# ServoController.net
KiCad netlist of a schematic drawn in EAGLE
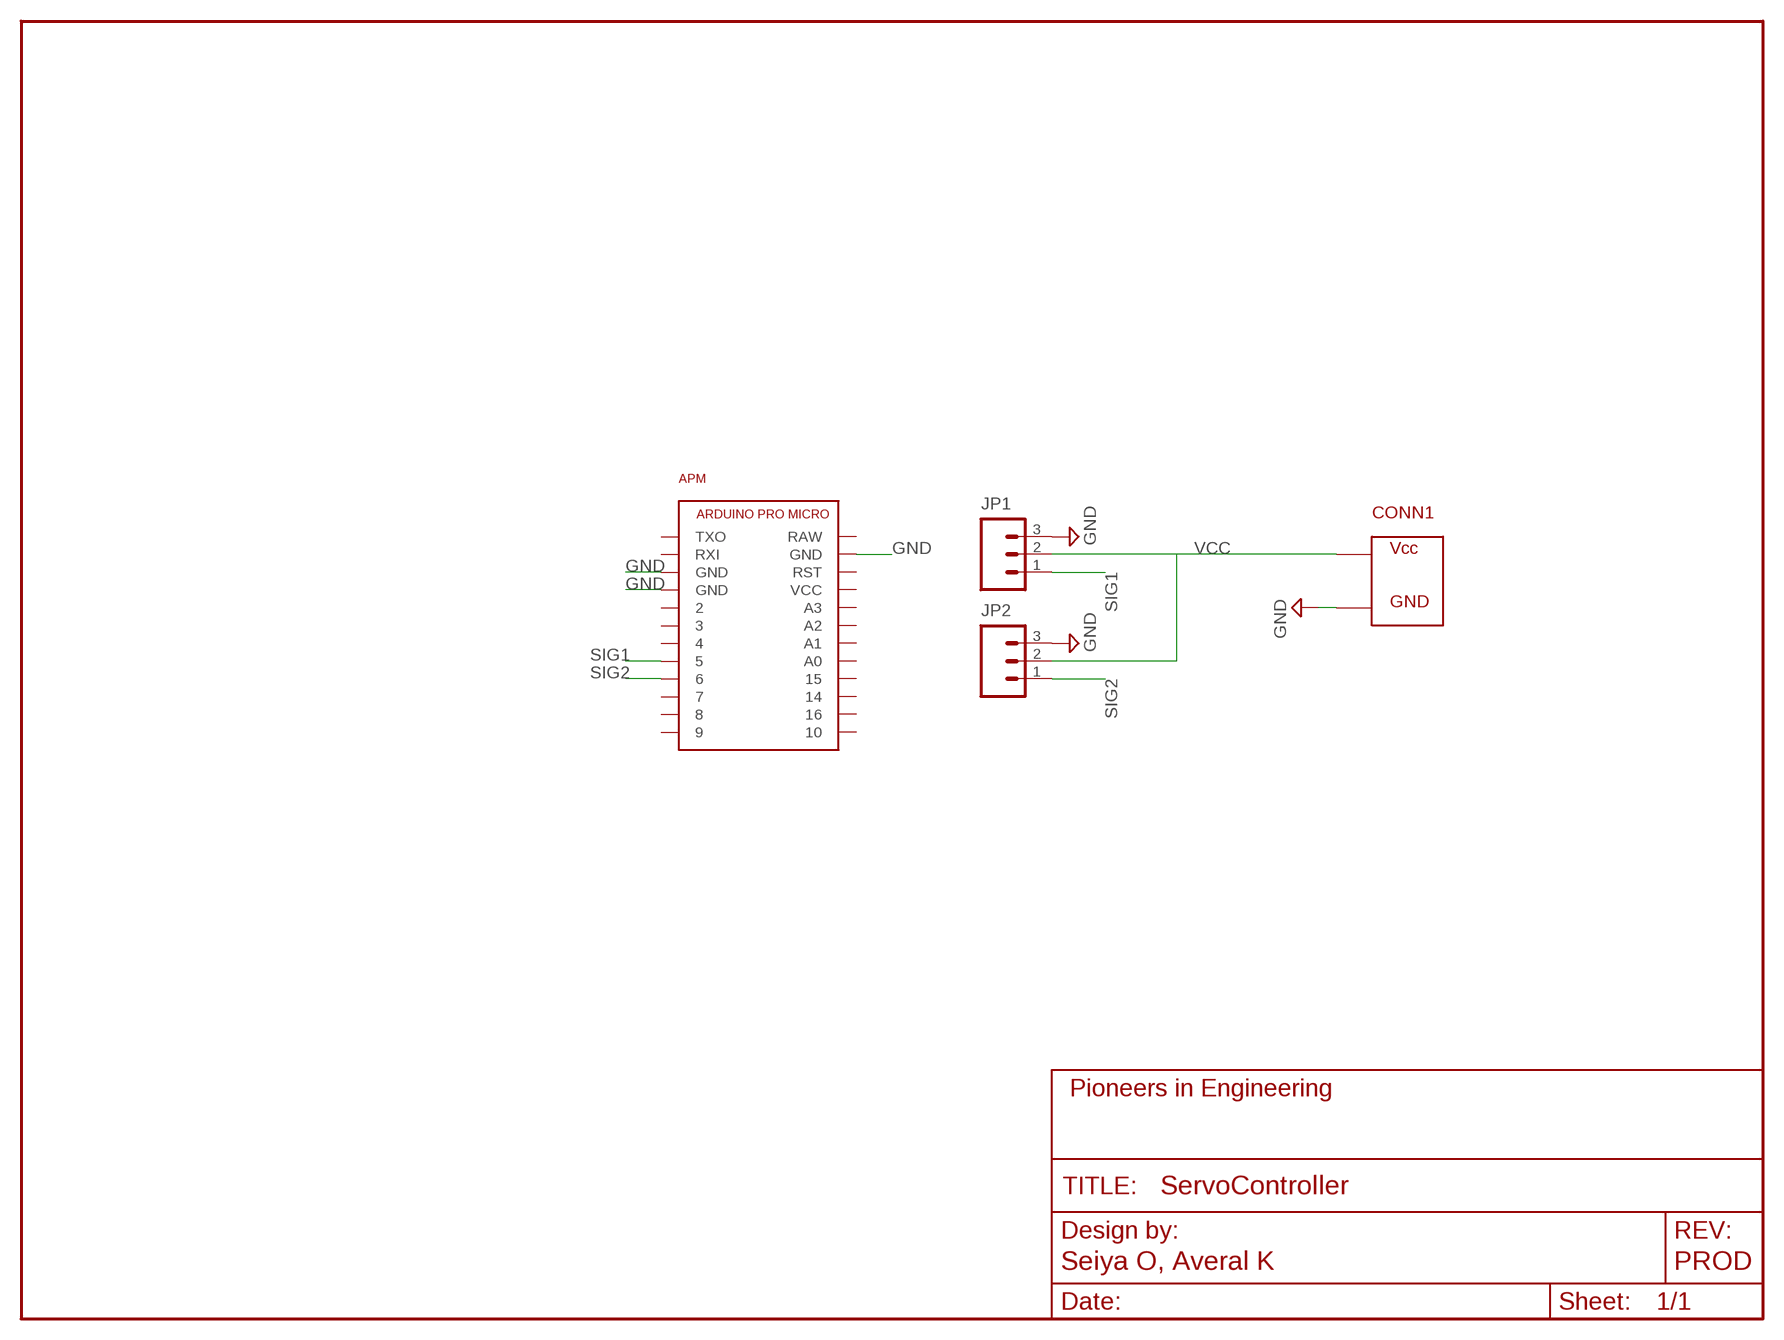
[diagram p0: schematic, sheet 1]

(export (version "E")
  (design (tool "Eeschema 10.0.6"))
  (components
    (comp (ref "APM")
      (value "ARDUINO_PRO_MICRO")
      (footprint "eagle-import:ARDUINO_PRO_MICRO")
      (fields
        (field (name "DISTRIBUTOR_PART_NUMBER") "32284746884")
        (field (name "MANUFACTURER") "Feiyang electronics")
      )
      (libsource (lib "eagle-import") (part "ARDUINO_PRO_MICRO"))
    )
    (comp (ref "CONN1")
      (value "ATX")
      (footprint "eagle-import:ATX")
      (libsource (lib "eagle-import") (part "ATX"))
    )
    (comp (ref "JP1")
      (value "M031X03-MTA")
      (footprint "eagle-import:1X03-MTA")
      (libsource (lib "eagle-import") (part "M031X03-MTA"))
    )
    (comp (ref "JP2")
      (value "M031X03-MTA")
      (footprint "eagle-import:1X03-MTA")
      (libsource (lib "eagle-import") (part "M031X03-MTA"))
    )
  )
  (nets
    (net (code "1") (name "/SIG1") (class "Default")
      (node (ref "APM") (pin "5") (pinfunction "5_5") (pintype "bidirectional"))
      (node (ref "JP1") (pin "1") (pinfunction "1_1") (pintype "passive"))
    )
    (net (code "2") (name "/SIG2") (class "Default")
      (node (ref "APM") (pin "6") (pinfunction "6_6") (pintype "bidirectional"))
      (node (ref "JP2") (pin "1") (pinfunction "1_1") (pintype "passive"))
    )
    (net (code "3") (name "/VCC") (class "Default")
      (node (ref "CONN1") (pin "P$1") (pinfunction "P$1_P$1") (pintype "power_in"))
      (node (ref "JP1") (pin "2") (pinfunction "2_2") (pintype "passive"))
      (node (ref "JP2") (pin "2") (pinfunction "2_2") (pintype "passive"))
    )
    (net (code "4") (name "GND") (class "Default")
      (node (ref "APM") (pin "GND@0") (pinfunction "GND_GND@0") (pintype "bidirectional"))
      (node (ref "APM") (pin "GND@1") (pinfunction "GND_GND@1") (pintype "bidirectional"))
      (node (ref "APM") (pin "GND@2") (pinfunction "GND_GND@2") (pintype "bidirectional"))
      (node (ref "CONN1") (pin "P$2") (pinfunction "P$2_P$2") (pintype "power_in"))
      (node (ref "JP1") (pin "3") (pinfunction "3_3") (pintype "passive"))
      (node (ref "JP2") (pin "3") (pinfunction "3_3") (pintype "passive"))
    )
    (net (code "5") (name "unconnected-(APM-Pad2)") (class "Default")
      (node (ref "APM") (pin "2") (pinfunction "2_2") (pintype "bidirectional"))
    )
    (net (code "6") (name "unconnected-(APM-Pad3)") (class "Default")
      (node (ref "APM") (pin "3") (pinfunction "3_3") (pintype "bidirectional"))
    )
    (net (code "7") (name "unconnected-(APM-Pad4)") (class "Default")
      (node (ref "APM") (pin "4") (pinfunction "4_4") (pintype "bidirectional"))
    )
    (net (code "8") (name "unconnected-(APM-Pad7)") (class "Default")
      (node (ref "APM") (pin "7") (pinfunction "7_7") (pintype "bidirectional"))
    )
    (net (code "9") (name "unconnected-(APM-Pad8)") (class "Default")
      (node (ref "APM") (pin "8") (pinfunction "8_8") (pintype "bidirectional"))
    )
    (net (code "10") (name "unconnected-(APM-Pad9)") (class "Default")
      (node (ref "APM") (pin "9") (pinfunction "9_9") (pintype "bidirectional"))
    )
    (net (code "11") (name "unconnected-(APM-Pad10)") (class "Default")
      (node (ref "APM") (pin "10") (pinfunction "10_10") (pintype "bidirectional"))
    )
    (net (code "12") (name "unconnected-(APM-Pad14)") (class "Default")
      (node (ref "APM") (pin "14") (pinfunction "14_14") (pintype "bidirectional"))
    )
    (net (code "13") (name "unconnected-(APM-Pad15)") (class "Default")
      (node (ref "APM") (pin "15") (pinfunction "15_15") (pintype "bidirectional"))
    )
    (net (code "14") (name "unconnected-(APM-Pad16)") (class "Default")
      (node (ref "APM") (pin "16") (pinfunction "16_16") (pintype "bidirectional"))
    )
    (net (code "15") (name "unconnected-(APM-PadA0)") (class "Default")
      (node (ref "APM") (pin "A0") (pinfunction "A0_A0") (pintype "bidirectional"))
    )
    (net (code "16") (name "unconnected-(APM-PadA1)") (class "Default")
      (node (ref "APM") (pin "A1") (pinfunction "A1_A1") (pintype "bidirectional"))
    )
    (net (code "17") (name "unconnected-(APM-PadA2)") (class "Default")
      (node (ref "APM") (pin "A2") (pinfunction "A2_A2") (pintype "bidirectional"))
    )
    (net (code "18") (name "unconnected-(APM-PadA3)") (class "Default")
      (node (ref "APM") (pin "A3") (pinfunction "A3_A3") (pintype "bidirectional"))
    )
    (net (code "19") (name "unconnected-(APM-PadRAW)") (class "Default")
      (node (ref "APM") (pin "RAW") (pinfunction "RAW_RAW") (pintype "bidirectional"))
    )
    (net (code "20") (name "unconnected-(APM-PadRST)") (class "Default")
      (node (ref "APM") (pin "RST") (pinfunction "RST_RST") (pintype "bidirectional"))
    )
    (net (code "21") (name "unconnected-(APM-PadRXI)") (class "Default")
      (node (ref "APM") (pin "RXI") (pinfunction "RXI_RXI") (pintype "bidirectional"))
    )
    (net (code "22") (name "unconnected-(APM-PadTXO)") (class "Default")
      (node (ref "APM") (pin "TXO") (pinfunction "TXO_TXO") (pintype "bidirectional"))
    )
    (net (code "23") (name "unconnected-(APM-PadVCC)") (class "Default")
      (node (ref "APM") (pin "VCC") (pinfunction "VCC_VCC") (pintype "bidirectional"))
    )
  )
)
